# ProPrj_LED__2025-12-02-21-30-15.net
KiCad netlist of a schematic drawn in EasyEDA Pro
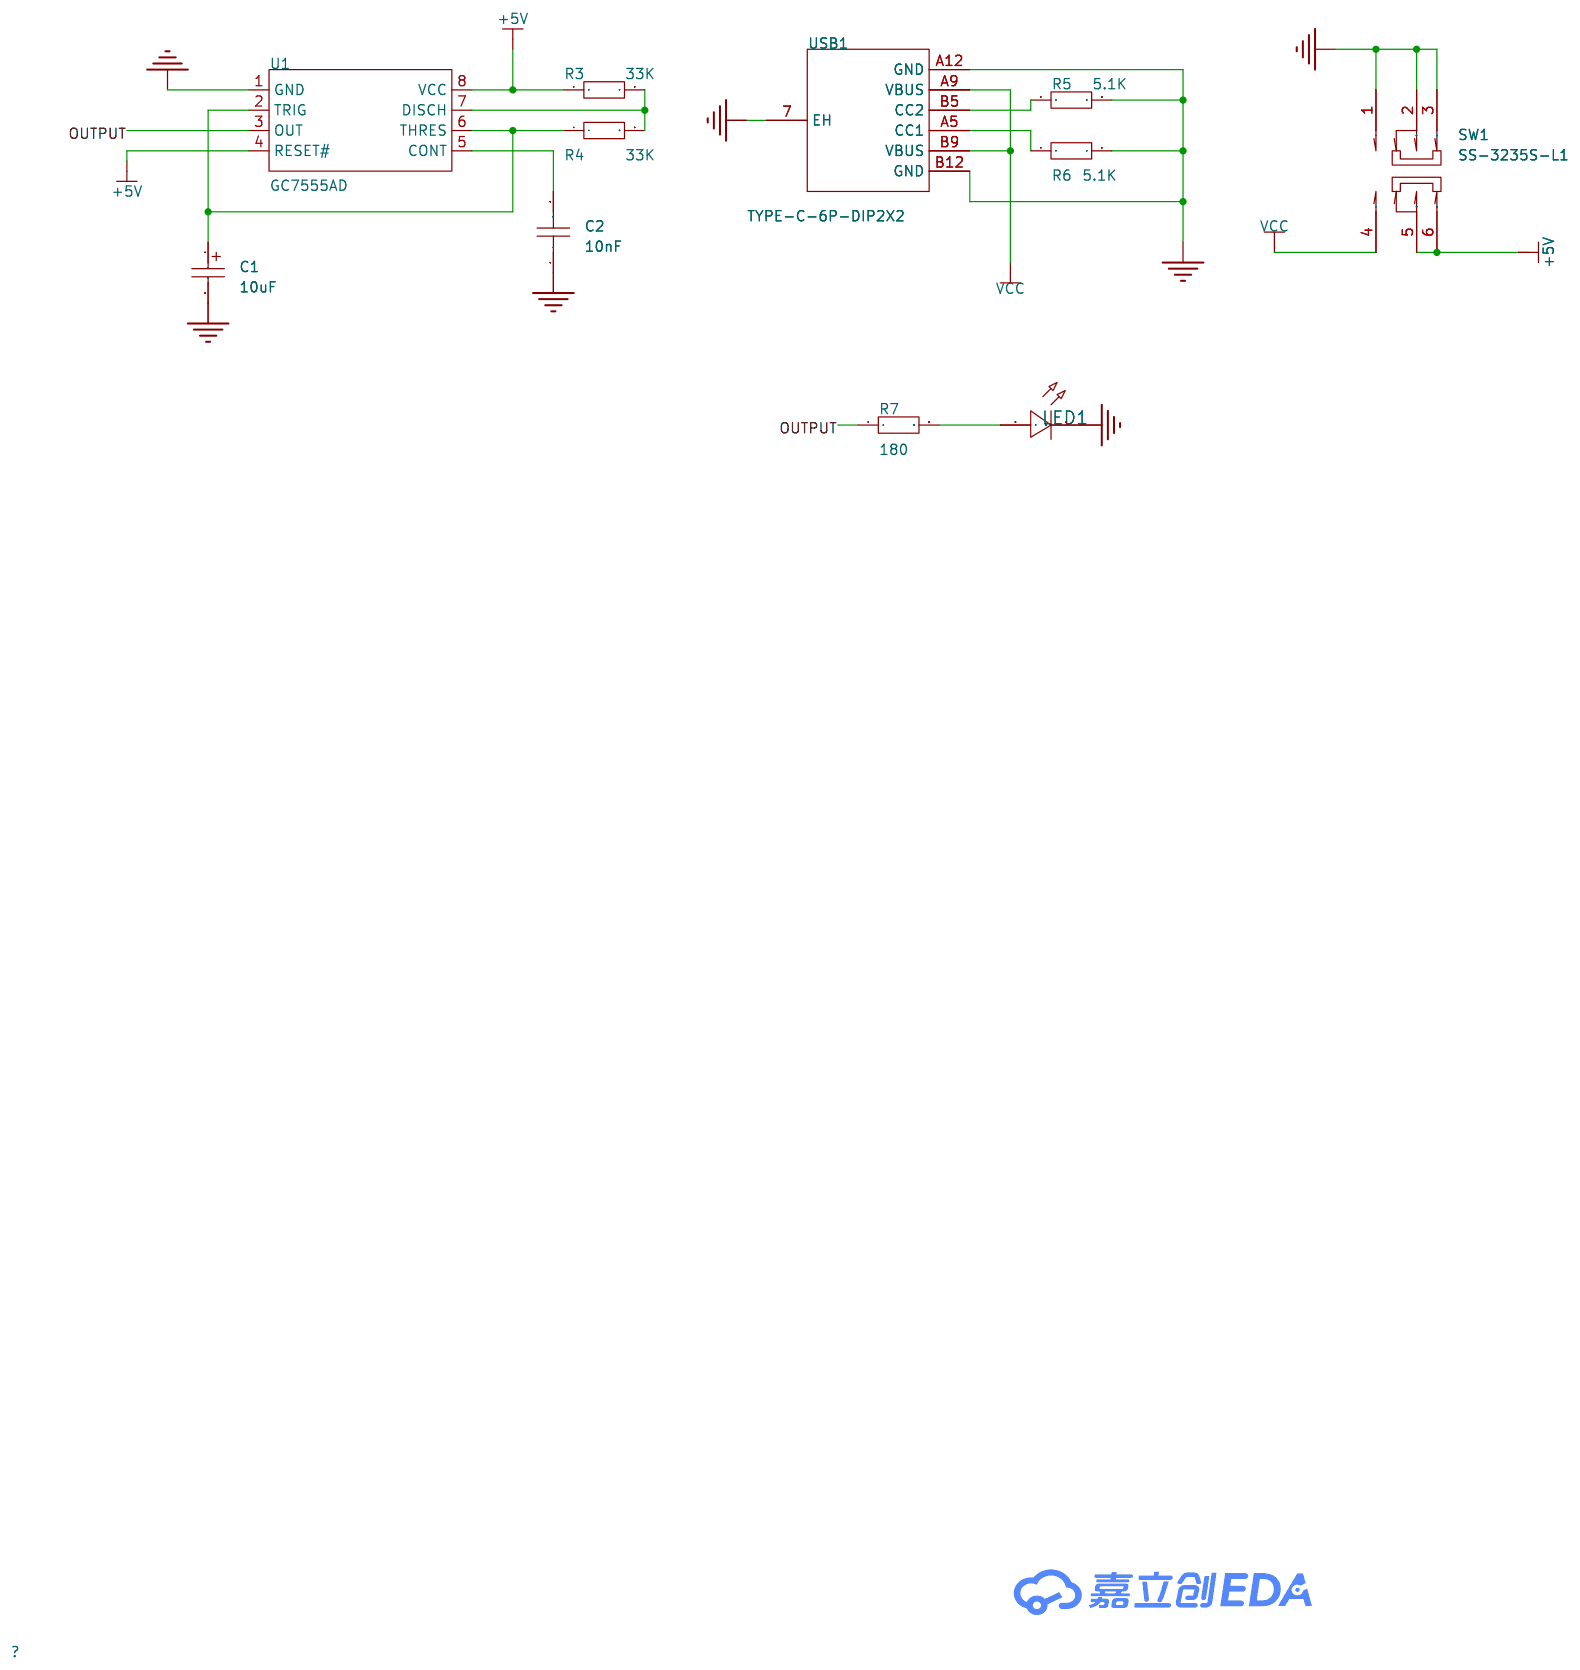
[diagram p0: schematic sheet]

(export (version "E")
  (design (tool "Eeschema 10.0.6"))
  (components
    (comp (ref "C1")
      (value "10uF")
      (footprint "easyedapro:C_Ele_SMD_3x5.4mm")
      (libsource (lib "easyedapro") (part "CAP"))
    )
    (comp (ref "C2")
      (value "10nF")
      (footprint "easyedapro:C0603")
      (libsource (lib "easyedapro") (part "Capacitance"))
    )
    (comp (ref "LED1")
      (value "~")
      (footprint "easyedapro:LED_0603")
      (libsource (lib "easyedapro") (part "LED_R"))
    )
    (comp (ref "R3") (value "33K") (footprint "easyedapro:R0805") (libsource (lib "easyedapro") (part "电阻")))
    (comp (ref "R4") (value "33K") (footprint "easyedapro:R0805") (libsource (lib "easyedapro") (part "电阻")))
    (comp (ref "R5") (value "5.1K") (footprint "easyedapro:R0805") (libsource (lib "easyedapro") (part "电阻")))
    (comp (ref "R6") (value "5.1K") (footprint "easyedapro:R0805") (libsource (lib "easyedapro") (part "电阻")))
    (comp (ref "R7") (value "180") (footprint "easyedapro:R0805") (libsource (lib "easyedapro") (part "电阻")))
    (comp (ref "SW1")
      (value "SS-3235S-L1")
      (footprint "easyedapro:SW-SMD_SS-3235S-LX")
      (description "电路结构:双刀双掷;安装方式:卧贴;开关颜色:黑色;额定电流:50mA;额定电压:12V;工作寿命:1万次;")
      (fields (field (name "Manufacturer") "XKB Connection(中国星坤)"))
      (libsource (lib "easyedapro") (part "SS-3235S-L1"))
    )
    (comp (ref "U1")
      (value "GC7555AD")
      (footprint "easyedapro:PDIP-8_L9.5-W6.4-P2.54-LS7.6-BL")
      (description "通用计时器：时基电路；计时；脉冲产生；满足用户（至少工业级）自主可控的需求。")
      (fields (field (name "Manufacturer") "Sungine(双竞集成)"))
      (libsource (lib "easyedapro") (part "GC7555AD"))
    )
    (comp (ref "USB1")
      (value "TYPE-C-6P-DIP2X2")
      (footprint "easyedapro:TYPE-C-SMD_TYPE-C-6P")
      (libsource (lib "easyedapro") (part "TYPE-C-6P-DIP2X2"))
    )
  )
  (nets
    (net (code "1") (name "+5V") (class "Default")
      (node (ref "R3") (pin "1") (pinfunction "1_1") (pintype "input"))
      (node (ref "SW1") (pin "5") (pinfunction "5_5") (pintype "unspecified"))
      (node (ref "SW1") (pin "6") (pinfunction "6_6") (pintype "unspecified"))
      (node (ref "U1") (pin "4") (pinfunction "RESET#_4") (pintype "unspecified"))
      (node (ref "U1") (pin "8") (pinfunction "VCC_8") (pintype "unspecified"))
    )
    (net (code "2") (name "/OUTPUT") (class "Default")
      (node (ref "R7") (pin "1") (pinfunction "1_1") (pintype "input"))
      (node (ref "U1") (pin "3") (pinfunction "OUT_3") (pintype "unspecified"))
    )
    (net (code "3") (name "GND") (class "Default")
      (node (ref "C1") (pin "2") (pinfunction "2_2") (pintype "input"))
      (node (ref "C2") (pin "1") (pinfunction "1_1") (pintype "input"))
      (node (ref "LED1") (pin "1") (pinfunction "C_1") (pintype "input"))
      (node (ref "R5") (pin "2") (pinfunction "2_2") (pintype "input"))
      (node (ref "R6") (pin "2") (pinfunction "2_2") (pintype "input"))
      (node (ref "SW1") (pin "1") (pinfunction "1_1") (pintype "unspecified"))
      (node (ref "SW1") (pin "2") (pinfunction "2_2") (pintype "unspecified"))
      (node (ref "SW1") (pin "3") (pinfunction "3_3") (pintype "unspecified"))
      (node (ref "U1") (pin "1") (pinfunction "GND_1") (pintype "unspecified"))
      (node (ref "USB1") (pin "7") (pinfunction "EH_7") (pintype "unspecified"))
      (node (ref "USB1") (pin "A12") (pinfunction "GND_A12") (pintype "unspecified"))
      (node (ref "USB1") (pin "B12") (pinfunction "GND_B12") (pintype "unspecified"))
    )
    (net (code "4") (name "Net-(LED1-A)") (class "Default")
      (node (ref "LED1") (pin "2") (pinfunction "A_2") (pintype "input"))
      (node (ref "R7") (pin "2") (pinfunction "2_2") (pintype "input"))
    )
    (net (code "5") (name "Net-(U1-CONT)") (class "Default")
      (node (ref "C2") (pin "2") (pinfunction "2_2") (pintype "input"))
      (node (ref "U1") (pin "5") (pinfunction "CONT_5") (pintype "unspecified"))
    )
    (net (code "6") (name "Net-(U1-DISCH)") (class "Default")
      (node (ref "R3") (pin "2") (pinfunction "2_2") (pintype "input"))
      (node (ref "R4") (pin "2") (pinfunction "2_2") (pintype "input"))
      (node (ref "U1") (pin "7") (pinfunction "DISCH_7") (pintype "unspecified"))
    )
    (net (code "7") (name "Net-(U1-THRES)") (class "Default")
      (node (ref "C1") (pin "1") (pinfunction "1_1") (pintype "input"))
      (node (ref "R4") (pin "1") (pinfunction "1_1") (pintype "input"))
      (node (ref "U1") (pin "2") (pinfunction "TRIG_2") (pintype "unspecified"))
      (node (ref "U1") (pin "6") (pinfunction "THRES_6") (pintype "unspecified"))
    )
    (net (code "8") (name "Net-(USB1-CC1)") (class "Default")
      (node (ref "R6") (pin "1") (pinfunction "1_1") (pintype "input"))
      (node (ref "USB1") (pin "A5") (pinfunction "CC1_A5") (pintype "unspecified"))
    )
    (net (code "9") (name "Net-(USB1-CC2)") (class "Default")
      (node (ref "R5") (pin "1") (pinfunction "1_1") (pintype "input"))
      (node (ref "USB1") (pin "B5") (pinfunction "CC2_B5") (pintype "unspecified"))
    )
    (net (code "10") (name "VCC") (class "Default")
      (node (ref "SW1") (pin "4") (pinfunction "4_4") (pintype "unspecified"))
      (node (ref "USB1") (pin "A9") (pinfunction "VBUS_A9") (pintype "unspecified"))
      (node (ref "USB1") (pin "B9") (pinfunction "VBUS_B9") (pintype "unspecified"))
    )
  )
)
